# STM32G473RET6_PINOUT.net
KiCad netlist of a schematic drawn in Altium Designer
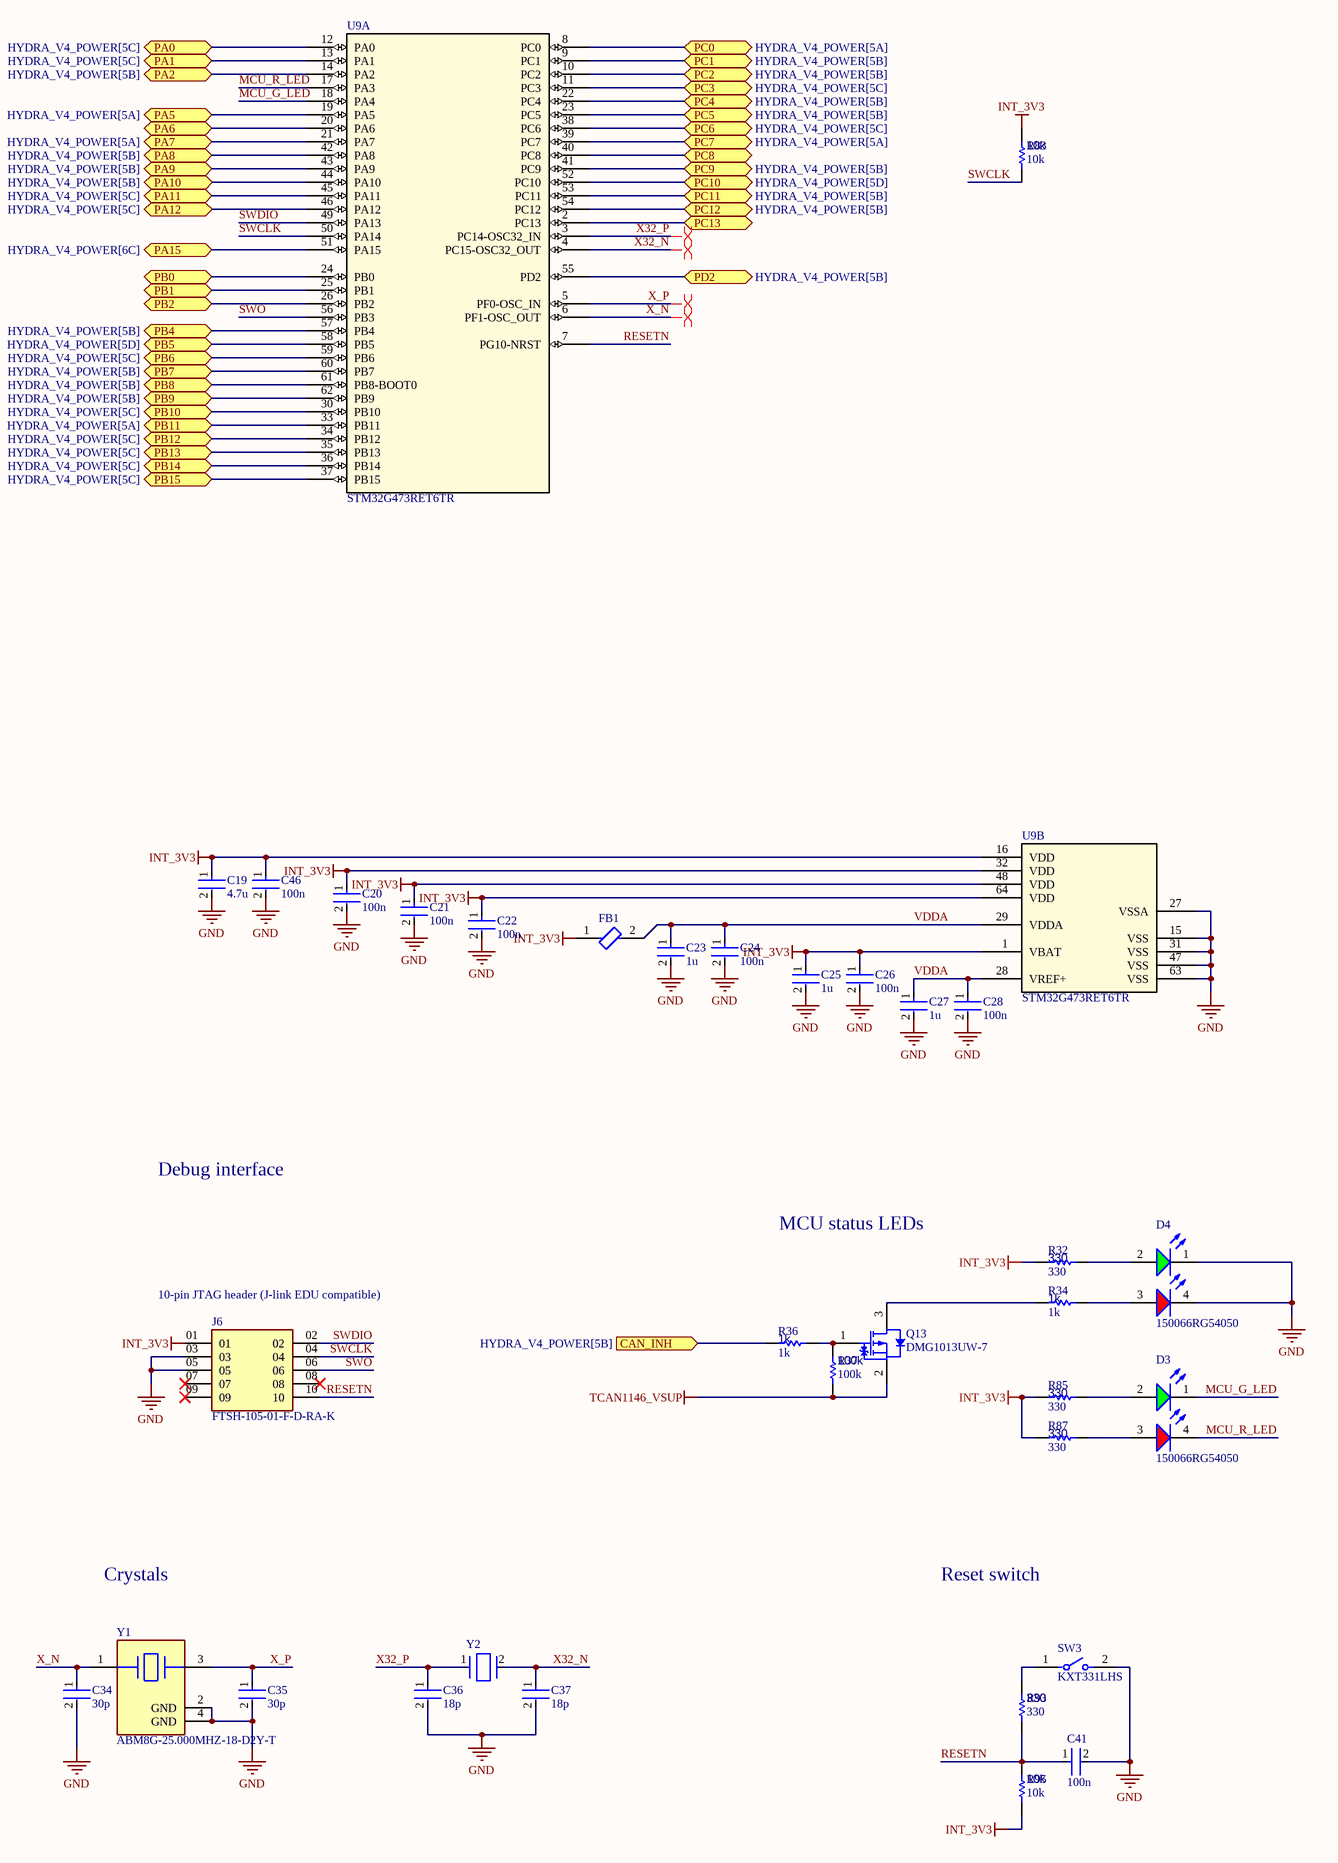
[diagram p0: STM32G473RET6_PINOUT.SchDoc]

(export (version "E")
  (design (tool "Eeschema 10.0.6"))
  (components
    (comp (ref "C19")
      (value "4.7u")
      (footprint "FP-0402-L_1_0_0_05-W_0_5-IPC_A")
      (description "LARGE PADS, 0402 CAP, CHANGE COMMENT TO MATCH REAL P/N")
      (libsource (lib "Space Concordia") (part "b4654b650e69147ec39a6b967a45e02"))
    )
    (comp (ref "C20")
      (value "100n")
      (footprint "FP-0402-L_1_0_0_05-W_0_5-IPC_A")
      (description "LARGE PADS, 0402 CAP, CHANGE COMMENT TO MATCH REAL P/N")
      (libsource (lib "Space Concordia") (part "b4654b650e69147ec39a6b967a45e02"))
    )
    (comp (ref "C21")
      (value "100n")
      (footprint "FP-0402-L_1_0_0_05-W_0_5-IPC_A")
      (description "LARGE PADS, 0402 CAP, CHANGE COMMENT TO MATCH REAL P/N")
      (libsource (lib "Space Concordia") (part "b4654b650e69147ec39a6b967a45e02"))
    )
    (comp (ref "C22")
      (value "100n")
      (footprint "FP-0402-L_1_0_0_05-W_0_5-IPC_A")
      (description "LARGE PADS, 0402 CAP, CHANGE COMMENT TO MATCH REAL P/N")
      (libsource (lib "Space Concordia") (part "b4654b650e69147ec39a6b967a45e02"))
    )
    (comp (ref "C23")
      (value "1u")
      (footprint "FP-0402-L_1_0_0_05-W_0_5-IPC_A")
      (description "LARGE PADS, 0402 CAP, CHANGE COMMENT TO MATCH REAL P/N")
      (libsource (lib "Space Concordia") (part "b4654b650e69147ec39a6b967a45e02"))
    )
    (comp (ref "C24")
      (value "100n")
      (footprint "FP-0402-L_1_0_0_05-W_0_5-IPC_A")
      (description "LARGE PADS, 0402 CAP, CHANGE COMMENT TO MATCH REAL P/N")
      (libsource (lib "Space Concordia") (part "b4654b650e69147ec39a6b967a45e02"))
    )
    (comp (ref "C25")
      (value "1u")
      (footprint "FP-0402-L_1_0_0_05-W_0_5-IPC_A")
      (description "LARGE PADS, 0402 CAP, CHANGE COMMENT TO MATCH REAL P/N")
      (libsource (lib "Space Concordia") (part "b4654b650e69147ec39a6b967a45e02"))
    )
    (comp (ref "C26")
      (value "100n")
      (footprint "FP-0402-L_1_0_0_05-W_0_5-IPC_A")
      (description "LARGE PADS, 0402 CAP, CHANGE COMMENT TO MATCH REAL P/N")
      (libsource (lib "Space Concordia") (part "b4654b650e69147ec39a6b967a45e02"))
    )
    (comp (ref "C27")
      (value "1u")
      (footprint "FP-0402-L_1_0_0_05-W_0_5-IPC_A")
      (description "LARGE PADS, 0402 CAP, CHANGE COMMENT TO MATCH REAL P/N")
      (libsource (lib "Space Concordia") (part "b4654b650e69147ec39a6b967a45e02"))
    )
    (comp (ref "C28")
      (value "100n")
      (footprint "FP-0402-L_1_0_0_05-W_0_5-IPC_A")
      (description "LARGE PADS, 0402 CAP, CHANGE COMMENT TO MATCH REAL P/N")
      (libsource (lib "Space Concordia") (part "b4654b650e69147ec39a6b967a45e02"))
    )
    (comp (ref "C34")
      (value "30p")
      (footprint "FP-0402-L_1_0_0_05-W_0_5-IPC_A")
      (description "LARGE PADS, 0402 CAP, CHANGE COMMENT TO MATCH REAL P/N")
      (libsource (lib "Space Concordia") (part "b4654b650e69147ec39a6b967a45e02"))
    )
    (comp (ref "C35")
      (value "30p")
      (footprint "FP-0402-L_1_0_0_05-W_0_5-IPC_A")
      (description "LARGE PADS, 0402 CAP, CHANGE COMMENT TO MATCH REAL P/N")
      (libsource (lib "Space Concordia") (part "b4654b650e69147ec39a6b967a45e02"))
    )
    (comp (ref "C36")
      (value "18p")
      (footprint "FP-0402-L_1_0_0_05-W_0_5-IPC_A")
      (description "LARGE PADS, 0402 CAP, CHANGE COMMENT TO MATCH REAL P/N")
      (libsource (lib "Space Concordia") (part "b4654b650e69147ec39a6b967a45e02"))
    )
    (comp (ref "C37")
      (value "18p")
      (footprint "FP-0402-L_1_0_0_05-W_0_5-IPC_A")
      (description "LARGE PADS, 0402 CAP, CHANGE COMMENT TO MATCH REAL P/N")
      (libsource (lib "Space Concordia") (part "b4654b650e69147ec39a6b967a45e02"))
    )
    (comp (ref "C41")
      (value "100n")
      (footprint "FP-0402-L_1_0_0_05-W_0_5-IPC_A")
      (description "LARGE PADS, 0402 CAP, CHANGE COMMENT TO MATCH REAL P/N")
      (libsource (lib "Space Concordia") (part "b4654b650e69147ec39a6b967a45e02"))
    )
    (comp (ref "C46")
      (value "100n")
      (footprint "FP-0402-L_1_0_0_05-W_0_5-IPC_A")
      (description "LARGE PADS, 0402 CAP, CHANGE COMMENT TO MATCH REAL P/N")
      (libsource (lib "Space Concordia") (part "b4654b650e69147ec39a6b967a45e02"))
    )
    (comp (ref "D3")
      (value "150066RG54050")
      (footprint "WL-SBCD_0606")
      (description "Led, Red/Grn, 180Mcd/230Mcd, 624Nm/525Nm Rohs Compliant: Yes")
      (fields (field (name "SOURCE") "rgled.SchLib"))
      (libsource (lib "Space Concordia") (part "CMP-004-00034-2"))
    )
    (comp (ref "D4")
      (value "150066RG54050")
      (footprint "WL-SBCD_0606")
      (description "Led, Red/Grn, 180Mcd/230Mcd, 624Nm/525Nm Rohs Compliant: Yes")
      (fields (field (name "SOURCE") "rgled.SchLib"))
      (libsource (lib "Space Concordia") (part "CMP-004-00034-2"))
    )
    (comp (ref "FB1")
      (value "BLM15PX601SN1D")
      (footprint "FP-BLM15-0_05-MFG")
      (description "Chip Ferrite Bead, 0402, 600Ω @ 100MHz, 0.23Ω, 25%, 900mA")
      (fields (field (name "TOLERANCE") "25%"))
      (libsource (lib "Altium Content Vault") (part "5f30dd21d616792df468990f7003faa"))
    )
    (comp (ref "J6")
      (value "FTSH-105-01-F-D-RA-K")
      (footprint "FTSH-105-01-F-D-RA-K-Footprint-1")
      (libsource (lib "Space Concordia") (part "FTSH-105-01-F-D-RA-K-Symbol-1"))
    )
    (comp (ref "Q13")
      (value "DMG1013UW-7")
      (footprint "DIOD-SOT323-3_V")
      (fields (field (name "MANUFACTURER") "Diodes Inc"))
      (libsource (lib "Altium Content Vault") (part "PEMOS-GSD-3_C"))
    )
    (comp (ref "R32")
      (value "330")
      (footprint "R0603B")
      (description "Resistor")
      (fields (field (name "ALTIUM_VALUE") "330"))
      (libsource (lib "Space Concordia") (part "Resistor"))
    )
    (comp (ref "R34")
      (value "1k")
      (footprint "R0603B")
      (description "Resistor")
      (fields (field (name "ALTIUM_VALUE") "1k"))
      (libsource (lib "Space Concordia") (part "Resistor"))
    )
    (comp (ref "R36")
      (value "1k")
      (footprint "R0603B")
      (description "Resistor")
      (fields (field (name "ALTIUM_VALUE") "1k"))
      (libsource (lib "Space Concordia") (part "Resistor"))
    )
    (comp (ref "R37")
      (value "100k")
      (footprint "R0603B")
      (description "Resistor")
      (fields (field (name "ALTIUM_VALUE") "100k"))
      (libsource (lib "Space Concordia") (part "Resistor"))
    )
    (comp (ref "R83")
      (value "10k")
      (footprint "R0603B")
      (description "Resistor")
      (fields (field (name "ALTIUM_VALUE") "10k"))
      (libsource (lib "Space Concordia") (part "Resistor"))
    )
    (comp (ref "R85")
      (value "330")
      (footprint "R0603B")
      (description "Resistor")
      (fields (field (name "ALTIUM_VALUE") "330"))
      (libsource (lib "Space Concordia") (part "Resistor"))
    )
    (comp (ref "R87")
      (value "330")
      (footprint "R0603B")
      (description "Resistor")
      (fields (field (name "ALTIUM_VALUE") "330"))
      (libsource (lib "Space Concordia") (part "Resistor"))
    )
    (comp (ref "R93")
      (value "330")
      (footprint "R0603B")
      (description "Resistor")
      (fields (field (name "ALTIUM_VALUE") "330"))
      (libsource (lib "Space Concordia") (part "Resistor"))
    )
    (comp (ref "R95")
      (value "10k")
      (footprint "R0603B")
      (description "Resistor")
      (fields (field (name "ALTIUM_VALUE") "10k"))
      (libsource (lib "Space Concordia") (part "Resistor"))
    )
    (comp (ref "SW3")
      (value "KXT331LHS")
      (footprint "FP-KXT331LHS-MFG")
      (description "SWITCH TACTILE SPST-NO 0.02A 15V")
      (libsource (lib "Altium Content Vault") (part "bb27bde45df87f1f469753f287ef5ae"))
    )
    (comp (ref "U9")
      (value "STM32G473RET6TR")
      (footprint "STM32G473RET6TR-Footprint-1")
      (description "MCU 32-Bit STM32 ARM Cortex-M4 RISC 512KB Flash 1.71V to 3.6V 64-Pin LQFP T/R")
      (libsource (lib "Space Concordia") (part "STM32G473RET6TR"))
    )
    (comp (ref "Y1")
      (value "ABM8G-25.000MHZ-18-D2Y-T")
      (footprint "FP-ABM8G-MFG")
      (description "Crystal 25MHz ±20ppm (Tol) ±30ppm (Stability) 18pF FUND 60Ω 4-Pin SMD T/R")
      (fields (field (name "TOLERANCE") "20ppm"))
      (libsource (lib "Altium Content Vault") (part "48e526d86b7f2615d98721063c72f49"))
    )
    (comp (ref "Y2")
      (value "ECS-.327-12.5-1210-TR")
      (footprint "FP-ECX-1210-MFG")
      (description "CRYSTAL 32.7680KHZ 12.5PF SMD")
      (fields
        (field (name "OCTOPART") "https://octopart.com/ecs-.327-12.5-1210-tr-ecs+international-81221340")
        (field (name "TOLERANCE") "20ppm")
      )
      (libsource (lib "Altium Content Vault") (part "99724985039315a44fd0d1401b84e49"))
    )
  )
  (nets
    (net (code "1") (name "/CAN_INH") (class "Default")
      (node (ref "R36") (pin "2") (pinfunction "2_2") (pintype "passive"))
    )
    (net (code "2") (name "/MCU_G_LED") (class "Default")
      (node (ref "D3") (pin "1") (pinfunction "K_1") (pintype "passive"))
      (node (ref "U9") (pin "18") (pinfunction "PA4_18") (pintype "bidirectional"))
    )
    (net (code "3") (name "/MCU_R_LED") (class "Default")
      (node (ref "D3") (pin "4") (pinfunction "K_4") (pintype "passive"))
      (node (ref "U9") (pin "17") (pinfunction "PA3_17") (pintype "bidirectional"))
    )
    (net (code "4") (name "/PA0") (class "Default")
      (node (ref "U9") (pin "12") (pinfunction "PA0_12") (pintype "bidirectional"))
    )
    (net (code "5") (name "/PA1") (class "Default")
      (node (ref "U9") (pin "13") (pinfunction "PA1_13") (pintype "bidirectional"))
    )
    (net (code "6") (name "/PA2") (class "Default")
      (node (ref "U9") (pin "14") (pinfunction "PA2_14") (pintype "bidirectional"))
    )
    (net (code "7") (name "/PA5") (class "Default")
      (node (ref "U9") (pin "19") (pinfunction "PA5_19") (pintype "bidirectional"))
    )
    (net (code "8") (name "/PA6") (class "Default")
      (node (ref "U9") (pin "20") (pinfunction "PA6_20") (pintype "bidirectional"))
    )
    (net (code "9") (name "/PA7") (class "Default")
      (node (ref "U9") (pin "21") (pinfunction "PA7_21") (pintype "bidirectional"))
    )
    (net (code "10") (name "/PA8") (class "Default")
      (node (ref "U9") (pin "42") (pinfunction "PA8_42") (pintype "bidirectional"))
    )
    (net (code "11") (name "/PA9") (class "Default")
      (node (ref "U9") (pin "43") (pinfunction "PA9_43") (pintype "bidirectional"))
    )
    (net (code "12") (name "/PA10") (class "Default")
      (node (ref "U9") (pin "44") (pinfunction "PA10_44") (pintype "bidirectional"))
    )
    (net (code "13") (name "/PA11") (class "Default")
      (node (ref "U9") (pin "45") (pinfunction "PA11_45") (pintype "bidirectional"))
    )
    (net (code "14") (name "/PA12") (class "Default")
      (node (ref "U9") (pin "46") (pinfunction "PA12_46") (pintype "bidirectional"))
    )
    (net (code "15") (name "/PA15") (class "Default")
      (node (ref "U9") (pin "51") (pinfunction "PA15_51") (pintype "bidirectional"))
    )
    (net (code "16") (name "/PB0") (class "Default")
      (node (ref "U9") (pin "24") (pinfunction "PB0_24") (pintype "bidirectional"))
    )
    (net (code "17") (name "/PB1") (class "Default")
      (node (ref "U9") (pin "25") (pinfunction "PB1_25") (pintype "bidirectional"))
    )
    (net (code "18") (name "/PB2") (class "Default")
      (node (ref "U9") (pin "26") (pinfunction "PB2_26") (pintype "bidirectional"))
    )
    (net (code "19") (name "/PB4") (class "Default")
      (node (ref "U9") (pin "57") (pinfunction "PB4_57") (pintype "bidirectional"))
    )
    (net (code "20") (name "/PB5") (class "Default")
      (node (ref "U9") (pin "58") (pinfunction "PB5_58") (pintype "bidirectional"))
    )
    (net (code "21") (name "/PB6") (class "Default")
      (node (ref "U9") (pin "59") (pinfunction "PB6_59") (pintype "bidirectional"))
    )
    (net (code "22") (name "/PB7") (class "Default")
      (node (ref "U9") (pin "60") (pinfunction "PB7_60") (pintype "bidirectional"))
    )
    (net (code "23") (name "/PB8") (class "Default")
      (node (ref "U9") (pin "61") (pinfunction "PB8-BOOT0_61") (pintype "bidirectional"))
    )
    (net (code "24") (name "/PB9") (class "Default")
      (node (ref "U9") (pin "62") (pinfunction "PB9_62") (pintype "bidirectional"))
    )
    (net (code "25") (name "/PB10") (class "Default")
      (node (ref "U9") (pin "30") (pinfunction "PB10_30") (pintype "bidirectional"))
    )
    (net (code "26") (name "/PB11") (class "Default")
      (node (ref "U9") (pin "33") (pinfunction "PB11_33") (pintype "bidirectional"))
    )
    (net (code "27") (name "/PB12") (class "Default")
      (node (ref "U9") (pin "34") (pinfunction "PB12_34") (pintype "bidirectional"))
    )
    (net (code "28") (name "/PB13") (class "Default")
      (node (ref "U9") (pin "35") (pinfunction "PB13_35") (pintype "bidirectional"))
    )
    (net (code "29") (name "/PB14") (class "Default")
      (node (ref "U9") (pin "36") (pinfunction "PB14_36") (pintype "bidirectional"))
    )
    (net (code "30") (name "/PB15") (class "Default")
      (node (ref "U9") (pin "37") (pinfunction "PB15_37") (pintype "bidirectional"))
    )
    (net (code "31") (name "/PC0") (class "Default")
      (node (ref "U9") (pin "8") (pinfunction "PC0_8") (pintype "bidirectional"))
    )
    (net (code "32") (name "/PC1") (class "Default")
      (node (ref "U9") (pin "9") (pinfunction "PC1_9") (pintype "bidirectional"))
    )
    (net (code "33") (name "/PC2") (class "Default")
      (node (ref "U9") (pin "10") (pinfunction "PC2_10") (pintype "bidirectional"))
    )
    (net (code "34") (name "/PC3") (class "Default")
      (node (ref "U9") (pin "11") (pinfunction "PC3_11") (pintype "bidirectional"))
    )
    (net (code "35") (name "/PC4") (class "Default")
      (node (ref "U9") (pin "22") (pinfunction "PC4_22") (pintype "bidirectional"))
    )
    (net (code "36") (name "/PC5") (class "Default")
      (node (ref "U9") (pin "23") (pinfunction "PC5_23") (pintype "bidirectional"))
    )
    (net (code "37") (name "/PC6") (class "Default")
      (node (ref "U9") (pin "38") (pinfunction "PC6_38") (pintype "bidirectional"))
    )
    (net (code "38") (name "/PC7") (class "Default")
      (node (ref "U9") (pin "39") (pinfunction "PC7_39") (pintype "bidirectional"))
    )
    (net (code "39") (name "/PC8") (class "Default")
      (node (ref "U9") (pin "40") (pinfunction "PC8_40") (pintype "bidirectional"))
    )
    (net (code "40") (name "/PC9") (class "Default")
      (node (ref "U9") (pin "41") (pinfunction "PC9_41") (pintype "bidirectional"))
    )
    (net (code "41") (name "/PC10") (class "Default")
      (node (ref "U9") (pin "52") (pinfunction "PC10_52") (pintype "bidirectional"))
    )
    (net (code "42") (name "/PC11") (class "Default")
      (node (ref "U9") (pin "53") (pinfunction "PC11_53") (pintype "bidirectional"))
    )
    (net (code "43") (name "/PC12") (class "Default")
      (node (ref "U9") (pin "54") (pinfunction "PC12_54") (pintype "bidirectional"))
    )
    (net (code "44") (name "/PC13") (class "Default")
      (node (ref "U9") (pin "2") (pinfunction "PC13_2") (pintype "bidirectional"))
    )
    (net (code "45") (name "/PD2") (class "Default")
      (node (ref "U9") (pin "55") (pinfunction "PD2_55") (pintype "bidirectional"))
    )
    (net (code "46") (name "/RESETN") (class "Default")
      (node (ref "C41") (pin "1") (pinfunction "1_1") (pintype "passive"))
      (node (ref "J6") (pin "10") (pinfunction "10_10") (pintype "passive"))
      (node (ref "R93") (pin "1") (pinfunction "1_1") (pintype "passive"))
      (node (ref "R95") (pin "2") (pinfunction "2_2") (pintype "passive"))
      (node (ref "U9") (pin "7") (pinfunction "PG10-NRST_7") (pintype "bidirectional"))
    )
    (net (code "47") (name "/SWCLK") (class "Default")
      (node (ref "J6") (pin "04") (pinfunction "04_04") (pintype "passive"))
      (node (ref "R83") (pin "1") (pinfunction "1_1") (pintype "passive"))
      (node (ref "U9") (pin "50") (pinfunction "PA14_50") (pintype "bidirectional"))
    )
    (net (code "48") (name "/SWDIO") (class "Default")
      (node (ref "J6") (pin "02") (pinfunction "02_02") (pintype "passive"))
      (node (ref "U9") (pin "49") (pinfunction "PA13_49") (pintype "bidirectional"))
    )
    (net (code "49") (name "/SWO") (class "Default")
      (node (ref "J6") (pin "06") (pinfunction "06_06") (pintype "passive"))
      (node (ref "U9") (pin "56") (pinfunction "PB3_56") (pintype "bidirectional"))
    )
    (net (code "50") (name "/VDDA") (class "Default")
      (node (ref "C23") (pin "1") (pinfunction "1_1") (pintype "passive"))
      (node (ref "C24") (pin "1") (pinfunction "1_1") (pintype "passive"))
      (node (ref "C27") (pin "1") (pinfunction "1_1") (pintype "passive"))
      (node (ref "C28") (pin "1") (pinfunction "1_1") (pintype "passive"))
      (node (ref "FB1") (pin "2") (pinfunction "2_2") (pintype "passive"))
      (node (ref "U9") (pin "28") (pinfunction "VREF+_28") (pintype "power_in"))
      (node (ref "U9") (pin "29") (pinfunction "VDDA_29") (pintype "power_in"))
    )
    (net (code "51") (name "/X32_N") (class "Default")
      (node (ref "C37") (pin "1") (pinfunction "1_1") (pintype "passive"))
      (node (ref "U9") (pin "4") (pinfunction "PC15-OSC32_OUT_4") (pintype "bidirectional"))
      (node (ref "Y2") (pin "2") (pinfunction "Out/In_2") (pintype "passive"))
    )
    (net (code "52") (name "/X32_P") (class "Default")
      (node (ref "C36") (pin "1") (pinfunction "1_1") (pintype "passive"))
      (node (ref "U9") (pin "3") (pinfunction "PC14-OSC32_IN_3") (pintype "bidirectional"))
      (node (ref "Y2") (pin "1") (pinfunction "In/Out_1") (pintype "passive"))
    )
    (net (code "53") (name "/X_N") (class "Default")
      (node (ref "C34") (pin "1") (pinfunction "1_1") (pintype "passive"))
      (node (ref "U9") (pin "6") (pinfunction "PF1-OSC_OUT_6") (pintype "bidirectional"))
      (node (ref "Y1") (pin "1") (pinfunction "1_1") (pintype "passive"))
    )
    (net (code "54") (name "/X_P") (class "Default")
      (node (ref "C35") (pin "1") (pinfunction "1_1") (pintype "passive"))
      (node (ref "U9") (pin "5") (pinfunction "PF0-OSC_IN_5") (pintype "bidirectional"))
      (node (ref "Y1") (pin "3") (pinfunction "3_3") (pintype "passive"))
    )
    (net (code "55") (name "GND") (class "Default")
      (node (ref "C19") (pin "2") (pinfunction "2_2") (pintype "passive"))
      (node (ref "C20") (pin "2") (pinfunction "2_2") (pintype "passive"))
      (node (ref "C21") (pin "2") (pinfunction "2_2") (pintype "passive"))
      (node (ref "C22") (pin "2") (pinfunction "2_2") (pintype "passive"))
      (node (ref "C23") (pin "2") (pinfunction "2_2") (pintype "passive"))
      (node (ref "C24") (pin "2") (pinfunction "2_2") (pintype "passive"))
      (node (ref "C25") (pin "2") (pinfunction "2_2") (pintype "passive"))
      (node (ref "C26") (pin "2") (pinfunction "2_2") (pintype "passive"))
      (node (ref "C27") (pin "2") (pinfunction "2_2") (pintype "passive"))
      (node (ref "C28") (pin "2") (pinfunction "2_2") (pintype "passive"))
      (node (ref "C34") (pin "2") (pinfunction "2_2") (pintype "passive"))
      (node (ref "C35") (pin "2") (pinfunction "2_2") (pintype "passive"))
      (node (ref "C36") (pin "2") (pinfunction "2_2") (pintype "passive"))
      (node (ref "C37") (pin "2") (pinfunction "2_2") (pintype "passive"))
      (node (ref "C41") (pin "2") (pinfunction "2_2") (pintype "passive"))
      (node (ref "C46") (pin "2") (pinfunction "2_2") (pintype "passive"))
      (node (ref "D4") (pin "1") (pinfunction "K_1") (pintype "passive"))
      (node (ref "D4") (pin "4") (pinfunction "K_4") (pintype "passive"))
      (node (ref "J6") (pin "03") (pinfunction "03_03") (pintype "passive"))
      (node (ref "J6") (pin "05") (pinfunction "05_05") (pintype "passive"))
      (node (ref "SW3") (pin "2") (pinfunction "2_2") (pintype "passive"))
      (node (ref "U9") (pin "15") (pinfunction "VSS_15") (pintype "power_in"))
      (node (ref "U9") (pin "27") (pinfunction "VSSA_27") (pintype "power_in"))
      (node (ref "U9") (pin "31") (pinfunction "VSS_31") (pintype "power_in"))
      (node (ref "U9") (pin "47") (pinfunction "VSS_47") (pintype "power_in"))
      (node (ref "U9") (pin "63") (pinfunction "VSS_63") (pintype "power_in"))
      (node (ref "Y1") (pin "2") (pinfunction "GND_2") (pintype "power_in"))
      (node (ref "Y1") (pin "4") (pinfunction "GND_4") (pintype "power_in"))
    )
    (net (code "56") (name "INT_3V3") (class "Default")
      (node (ref "C19") (pin "1") (pinfunction "1_1") (pintype "passive"))
      (node (ref "C20") (pin "1") (pinfunction "1_1") (pintype "passive"))
      (node (ref "C21") (pin "1") (pinfunction "1_1") (pintype "passive"))
      (node (ref "C22") (pin "1") (pinfunction "1_1") (pintype "passive"))
      (node (ref "C25") (pin "1") (pinfunction "1_1") (pintype "passive"))
      (node (ref "C26") (pin "1") (pinfunction "1_1") (pintype "passive"))
      (node (ref "C46") (pin "1") (pinfunction "1_1") (pintype "passive"))
      (node (ref "FB1") (pin "1") (pinfunction "1_1") (pintype "passive"))
      (node (ref "J6") (pin "01") (pinfunction "01_01") (pintype "passive"))
      (node (ref "R32") (pin "2") (pinfunction "2_2") (pintype "passive"))
      (node (ref "R83") (pin "2") (pinfunction "2_2") (pintype "passive"))
      (node (ref "R85") (pin "2") (pinfunction "2_2") (pintype "passive"))
      (node (ref "R87") (pin "2") (pinfunction "2_2") (pintype "passive"))
      (node (ref "R95") (pin "1") (pinfunction "1_1") (pintype "passive"))
      (node (ref "U9") (pin "1") (pinfunction "VBAT_1") (pintype "power_in"))
      (node (ref "U9") (pin "16") (pinfunction "VDD_16") (pintype "power_in"))
      (node (ref "U9") (pin "32") (pinfunction "VDD_32") (pintype "power_in"))
      (node (ref "U9") (pin "48") (pinfunction "VDD_48") (pintype "power_in"))
      (node (ref "U9") (pin "64") (pinfunction "VDD_64") (pintype "power_in"))
    )
    (net (code "57") (name "Net-(D3-A-Pad2)") (class "Default")
      (node (ref "D3") (pin "2") (pinfunction "A_2") (pintype "passive"))
      (node (ref "R85") (pin "1") (pinfunction "1_1") (pintype "passive"))
    )
    (net (code "58") (name "Net-(D3-A-Pad3)") (class "Default")
      (node (ref "D3") (pin "3") (pinfunction "A_3") (pintype "passive"))
      (node (ref "R87") (pin "1") (pinfunction "1_1") (pintype "passive"))
    )
    (net (code "59") (name "Net-(D4-A-Pad2)") (class "Default")
      (node (ref "D4") (pin "2") (pinfunction "A_2") (pintype "passive"))
      (node (ref "R32") (pin "1") (pinfunction "1_1") (pintype "passive"))
    )
    (net (code "60") (name "Net-(D4-A-Pad3)") (class "Default")
      (node (ref "D4") (pin "3") (pinfunction "A_3") (pintype "passive"))
      (node (ref "R34") (pin "1") (pinfunction "1_1") (pintype "passive"))
    )
    (net (code "61") (name "Net-(Q13-D)") (class "Default")
      (node (ref "Q13") (pin "3") (pinfunction "D_3") (pintype "passive"))
      (node (ref "R34") (pin "2") (pinfunction "2_2") (pintype "passive"))
    )
    (net (code "62") (name "Net-(Q13-G)") (class "Default")
      (node (ref "Q13") (pin "1") (pinfunction "G_1") (pintype "passive"))
      (node (ref "R36") (pin "1") (pinfunction "1_1") (pintype "passive"))
      (node (ref "R37") (pin "1") (pinfunction "1_1") (pintype "passive"))
    )
    (net (code "63") (name "Net-(R93-Pad2)") (class "Default")
      (node (ref "R93") (pin "2") (pinfunction "2_2") (pintype "passive"))
      (node (ref "SW3") (pin "1") (pinfunction "1_1") (pintype "passive"))
    )
    (net (code "64") (name "TCAN1146_VSUP") (class "Default")
      (node (ref "Q13") (pin "2") (pinfunction "S_2") (pintype "passive"))
      (node (ref "R37") (pin "2") (pinfunction "2_2") (pintype "passive"))
    )
    (net (code "65") (name "unconnected-(J6-Pad07)") (class "Default")
      (node (ref "J6") (pin "07") (pinfunction "07_07") (pintype "passive+no_connect"))
    )
    (net (code "66") (name "unconnected-(J6-Pad08)") (class "Default")
      (node (ref "J6") (pin "08") (pinfunction "08_08") (pintype "passive+no_connect"))
    )
    (net (code "67") (name "unconnected-(J6-Pad09)") (class "Default")
      (node (ref "J6") (pin "09") (pinfunction "09_09") (pintype "passive+no_connect"))
    )
  )
)
